# GPS.net
KiCad netlist of a schematic drawn in Altium Designer
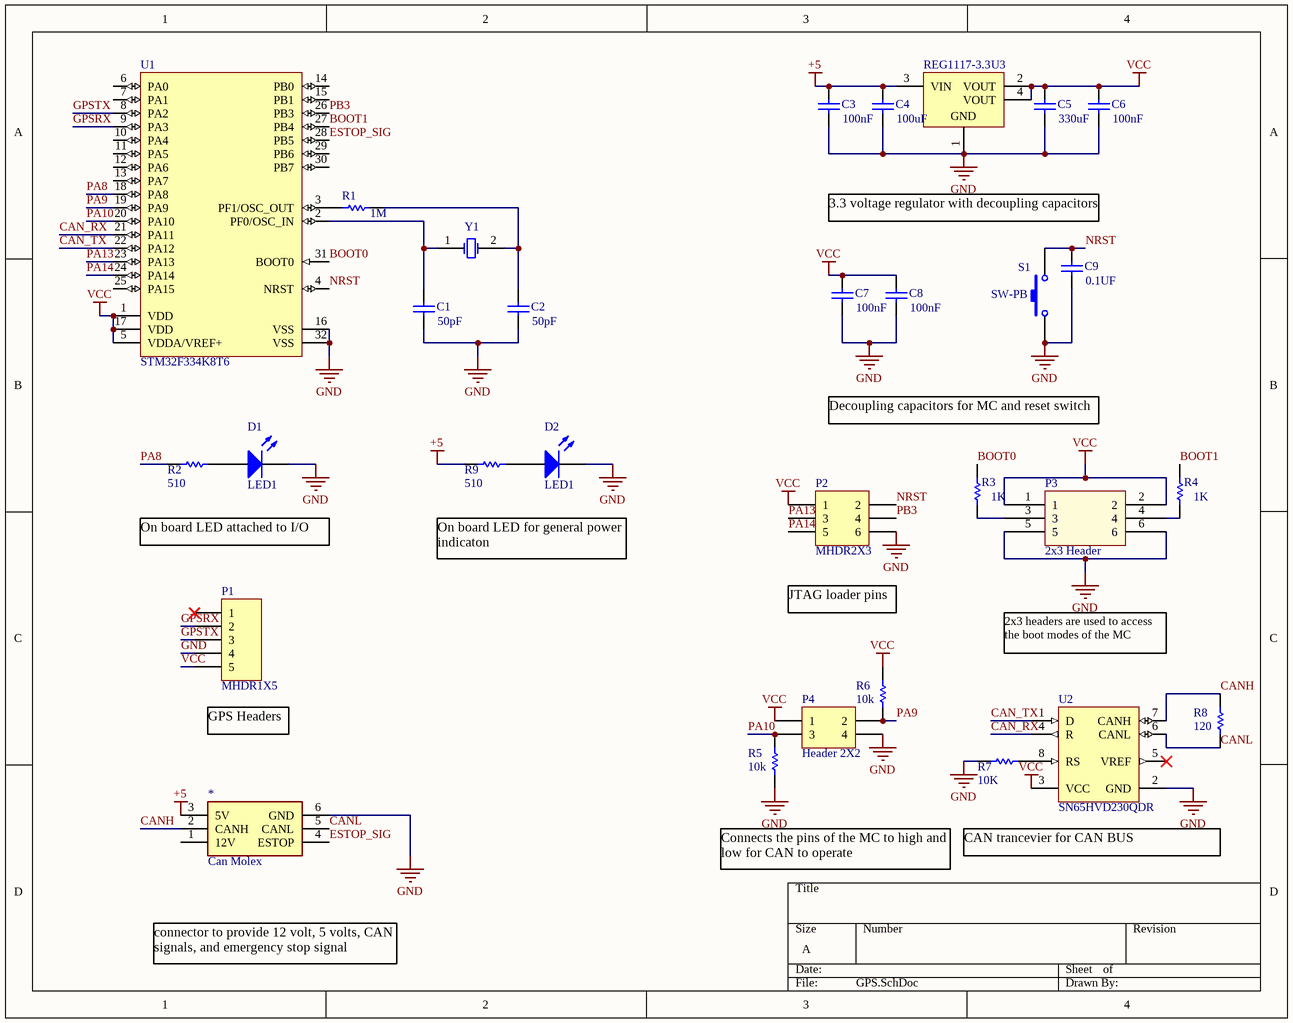
[diagram p0: GPS.SchDoc]

(export (version "E")
  (design (tool "Eeschema 10.0.6"))
  (components
    (comp (ref "*")
      (value "Can Molex")
      (footprint "Can Molex-Footprint-1")
      (description "can molex for IGVC")
      (libsource (lib "OU Competitive Robotics Club") (part "Can Molex-Symbol-1"))
    )
    (comp (ref "C1")
      (value "50pF")
      (footprint "6-0805_L")
      (description "Capacitor")
      (fields (field (name "Comment") "Cap") (field (name "PUBLISHER") "Altium Limited"))
      (libsource (lib "Miscellaneous Devices") (part "Cap"))
    )
    (comp (ref "C2")
      (value "50pF")
      (footprint "6-0805_L")
      (description "Capacitor")
      (fields (field (name "Comment") "Cap") (field (name "PUBLISHER") "Altium Limited"))
      (libsource (lib "Miscellaneous Devices") (part "Cap"))
    )
    (comp (ref "C3")
      (value "100nF")
      (footprint "6-0805_L")
      (description "Capacitor")
      (fields (field (name "Comment") "Cap") (field (name "PUBLISHER") "Altium Limited"))
      (libsource (lib "Miscellaneous Devices") (part "Cap"))
    )
    (comp (ref "C4")
      (value "100uF")
      (footprint "6-0805_L")
      (description "Capacitor")
      (fields (field (name "Comment") "Cap") (field (name "PUBLISHER") "Altium Limited"))
      (libsource (lib "Miscellaneous Devices") (part "Cap"))
    )
    (comp (ref "C5")
      (value "330uF")
      (footprint "6-0805_L")
      (description "Capacitor")
      (fields (field (name "Comment") "Cap") (field (name "PUBLISHER") "Altium Limited"))
      (libsource (lib "Miscellaneous Devices") (part "Cap"))
    )
    (comp (ref "C6")
      (value "100nF")
      (footprint "6-0805_L")
      (description "Capacitor")
      (fields (field (name "Comment") "Cap") (field (name "PUBLISHER") "Altium Limited"))
      (libsource (lib "Miscellaneous Devices") (part "Cap"))
    )
    (comp (ref "C7")
      (value "100nF")
      (footprint "6-0805_L")
      (description "Capacitor")
      (fields (field (name "Comment") "Cap") (field (name "PUBLISHER") "Altium Limited"))
      (libsource (lib "Miscellaneous Devices") (part "Cap"))
    )
    (comp (ref "C8")
      (value "100nF")
      (footprint "6-0805_L")
      (description "Capacitor")
      (fields (field (name "Comment") "Cap") (field (name "PUBLISHER") "Altium Limited"))
      (libsource (lib "Miscellaneous Devices") (part "Cap"))
    )
    (comp (ref "C9")
      (value "0.1UF")
      (footprint "6-0805_L")
      (description "Capacitor")
      (fields (field (name "Comment") "Cap") (field (name "PUBLISHER") "Altium Limited"))
      (libsource (lib "Miscellaneous Devices") (part "Cap"))
    )
    (comp (ref "D1")
      (value "LED1")
      (footprint "6-0805_L")
      (description "Typical RED GaAs LED")
      (fields (field (name "PUBLISHER") "Altium Limited"))
      (libsource (lib "Miscellaneous Devices") (part "LED1"))
    )
    (comp (ref "D2")
      (value "LED1")
      (footprint "6-0805_L")
      (description "Typical RED GaAs LED")
      (fields (field (name "PUBLISHER") "Altium Limited"))
      (libsource (lib "Miscellaneous Devices") (part "LED1"))
    )
    (comp (ref "P1")
      (value "MHDR1X5")
      (footprint "MHDR1X5")
      (description "Header, 5-Pin")
      (fields (field (name "PUBLISHER") "Altium Limited"))
      (libsource (lib "Miscellaneous Connectors") (part "MHDR1X5"))
    )
    (comp (ref "P2")
      (value "MHDR2X3")
      (footprint "HDR2X3")
      (description "Header, 3-Pin, Dual row")
      (fields (field (name "PUBLISHER") "Altium Limited"))
      (libsource (lib "Miscellaneous Connectors") (part "MHDR2X3"))
    )
    (comp (ref "P3")
      (value "2x3 Header")
      (footprint "HDR2X3")
      (libsource (lib "Schlib1") (part "2x3 Header"))
    )
    (comp (ref "P4")
      (value "Header 2X2")
      (footprint "HDR2X2")
      (description "Header, 2-Pin, Dual row")
      (fields (field (name "PUBLISHER") "Altium Limited"))
      (libsource (lib "Miscellaneous Connectors") (part "Header 2X2"))
    )
    (comp (ref "R1")
      (value "1M")
      (footprint "1608[0603]")
      (description "Resistor")
      (fields (field (name "Comment") "Res1") (field (name "PUBLISHER") "Altium Limited"))
      (libsource (lib "Miscellaneous Devices") (part "Res1"))
    )
    (comp (ref "R2")
      (value "510")
      (footprint "1608[0603]")
      (description "Resistor")
      (fields (field (name "Comment") "Res1") (field (name "PUBLISHER") "Altium Limited"))
      (libsource (lib "Miscellaneous Devices") (part "Res1"))
    )
    (comp (ref "R3")
      (value "1K")
      (footprint "1608[0603]")
      (description "Resistor")
      (fields (field (name "Comment") "Res1") (field (name "PUBLISHER") "Altium Limited"))
      (libsource (lib "Miscellaneous Devices") (part "Res1"))
    )
    (comp (ref "R4")
      (value "1K")
      (footprint "1608[0603]")
      (description "Resistor")
      (fields (field (name "Comment") "Res1") (field (name "PUBLISHER") "Altium Limited"))
      (libsource (lib "Miscellaneous Devices") (part "Res1"))
    )
    (comp (ref "R5")
      (value "10k")
      (footprint "1608[0603]")
      (description "Resistor")
      (fields (field (name "Comment") "Res1") (field (name "PUBLISHER") "Altium Limited"))
      (libsource (lib "Miscellaneous Devices") (part "Res1"))
    )
    (comp (ref "R6")
      (value "10k")
      (footprint "1608[0603]")
      (description "Resistor")
      (fields (field (name "Comment") "Res1") (field (name "PUBLISHER") "Altium Limited"))
      (libsource (lib "Miscellaneous Devices") (part "Res1"))
    )
    (comp (ref "R7")
      (value "10K")
      (footprint "1608[0603]")
      (description "Resistor")
      (fields (field (name "Comment") "Res1") (field (name "PUBLISHER") "Altium Limited"))
      (libsource (lib "Miscellaneous Devices") (part "Res1"))
    )
    (comp (ref "R8")
      (value "120")
      (footprint "1608[0603]")
      (description "Resistor")
      (fields (field (name "Comment") "Res1") (field (name "PUBLISHER") "Altium Limited"))
      (libsource (lib "Miscellaneous Devices") (part "Res1"))
    )
    (comp (ref "R9")
      (value "510")
      (footprint "1608[0603]")
      (description "Resistor")
      (fields (field (name "Comment") "Res1") (field (name "PUBLISHER") "Altium Limited"))
      (libsource (lib "Miscellaneous Devices") (part "Res1"))
    )
    (comp (ref "S1")
      (value "SW-PB")
      (footprint "GPSLib:Push Switch 3x6x2.5")
      (description "Switch")
      (fields (field (name "PUBLISHER") "Altium Limited"))
      (libsource (lib "Miscellaneous Devices") (part "SW-PB"))
    )
    (comp (ref "U1")
      (value "STM32F334K8T6")
      (footprint "STM-LQFP32_M")
      (libsource (lib "Altium Content Vault") (part "MC-ARM-STM32F334-LQFP32"))
    )
    (comp (ref "U2")
      (value "SN65HVD230QDR")
      (footprint "D0008A_L")
      (fields (field (name "MANUFACTURER") "Texas Instruments"))
      (libsource (lib "Altium Content Vault") (part "TI-SN65HVD230Q-SOIC_D-8"))
    )
    (comp (ref "U3")
      (value "REG1117-3.3")
      (footprint "DCY0004A_M")
      (fields (field (name "MANUFACTURER") "Texas Instruments"))
      (libsource (lib "Altium Content Vault") (part "TI-REG1117-XXXX"))
    )
    (comp (ref "Y1")
      (value "XTAL")
      (footprint "Crystal 11.4 x 4.7 x 4.2 mm")
      (description "Crystal Oscillator")
      (fields (field (name "PUBLISHER") "Altium Limited"))
      (libsource (lib "Miscellaneous Devices") (part "XTAL"))
    )
  )
  (nets
    (net (code "1") (name "+5") (class "Default")
      (node (ref "*") (pin "3") (pinfunction "5V_3") (pintype "passive"))
      (node (ref "C3") (pin "2") (pinfunction "2_2") (pintype "passive"))
      (node (ref "C4") (pin "2") (pinfunction "2_2") (pintype "passive"))
      (node (ref "R9") (pin "1") (pinfunction "1_1") (pintype "passive"))
      (node (ref "U3") (pin "3") (pinfunction "VIN_3") (pintype "power_in"))
    )
    (net (code "2") (name "/BOOT0") (class "Default")
      (node (ref "R3") (pin "2") (pinfunction "2_2") (pintype "passive"))
      (node (ref "U1") (pin "31") (pinfunction "BOOT0_31") (pintype "input"))
    )
    (net (code "3") (name "/BOOT1") (class "Default")
      (node (ref "R4") (pin "2") (pinfunction "2_2") (pintype "passive"))
      (node (ref "U1") (pin "27") (pinfunction "PB4_27") (pintype "bidirectional"))
    )
    (net (code "4") (name "/CANH") (class "Default")
      (node (ref "*") (pin "2") (pinfunction "CANH_2") (pintype "passive"))
      (node (ref "R8") (pin "2") (pinfunction "2_2") (pintype "passive"))
      (node (ref "U2") (pin "7") (pinfunction "CANH_7") (pintype "bidirectional"))
    )
    (net (code "5") (name "/CANL") (class "Default")
      (node (ref "*") (pin "5") (pinfunction "CANL_5") (pintype "passive"))
      (node (ref "R8") (pin "1") (pinfunction "1_1") (pintype "passive"))
      (node (ref "U2") (pin "6") (pinfunction "CANL_6") (pintype "bidirectional"))
    )
    (net (code "6") (name "/CAN_RX") (class "Default")
      (node (ref "U1") (pin "21") (pinfunction "PA11_21") (pintype "bidirectional"))
      (node (ref "U2") (pin "4") (pinfunction "R_4") (pintype "output"))
    )
    (net (code "7") (name "/CAN_TX") (class "Default")
      (node (ref "U1") (pin "22") (pinfunction "PA12_22") (pintype "bidirectional"))
      (node (ref "U2") (pin "1") (pinfunction "D_1") (pintype "input"))
    )
    (net (code "8") (name "/ESTOP_SIG") (class "Default")
      (node (ref "*") (pin "4") (pinfunction "ESTOP_4") (pintype "passive"))
      (node (ref "U1") (pin "28") (pinfunction "PB5_28") (pintype "bidirectional"))
    )
    (net (code "9") (name "/GPSRX") (class "Default")
      (node (ref "P1") (pin "2") (pinfunction "2_2") (pintype "passive"))
      (node (ref "U1") (pin "9") (pinfunction "PA3_9") (pintype "bidirectional"))
    )
    (net (code "10") (name "/GPSTX") (class "Default")
      (node (ref "P1") (pin "3") (pinfunction "3_3") (pintype "passive"))
      (node (ref "U1") (pin "8") (pinfunction "PA2_8") (pintype "bidirectional"))
    )
    (net (code "11") (name "/NRST") (class "Default")
      (node (ref "C9") (pin "2") (pinfunction "2_2") (pintype "passive"))
      (node (ref "P2") (pin "2") (pinfunction "2_2") (pintype "passive"))
      (node (ref "S1") (pin "2") (pinfunction "2_2") (pintype "passive"))
      (node (ref "U1") (pin "4") (pinfunction "NRST_4") (pintype "bidirectional"))
    )
    (net (code "12") (name "/PA8") (class "Default")
      (node (ref "R2") (pin "1") (pinfunction "1_1") (pintype "passive"))
      (node (ref "U1") (pin "18") (pinfunction "PA8_18") (pintype "bidirectional"))
    )
    (net (code "13") (name "/PA9") (class "Default")
      (node (ref "P4") (pin "2") (pinfunction "2_2") (pintype "passive"))
      (node (ref "R6") (pin "1") (pinfunction "1_1") (pintype "passive"))
      (node (ref "U1") (pin "19") (pinfunction "PA9_19") (pintype "bidirectional"))
    )
    (net (code "14") (name "/PA10") (class "Default")
      (node (ref "P4") (pin "3") (pinfunction "3_3") (pintype "passive"))
      (node (ref "R5") (pin "2") (pinfunction "2_2") (pintype "passive"))
      (node (ref "U1") (pin "20") (pinfunction "PA10_20") (pintype "bidirectional"))
    )
    (net (code "15") (name "/PA13") (class "Default")
      (node (ref "P2") (pin "3") (pinfunction "3_3") (pintype "passive"))
      (node (ref "U1") (pin "23") (pinfunction "PA13_23") (pintype "bidirectional"))
    )
    (net (code "16") (name "/PA14") (class "Default")
      (node (ref "P2") (pin "5") (pinfunction "5_5") (pintype "passive"))
      (node (ref "U1") (pin "24") (pinfunction "PA14_24") (pintype "bidirectional"))
    )
    (net (code "17") (name "/PB3") (class "Default")
      (node (ref "P2") (pin "4") (pinfunction "4_4") (pintype "passive"))
      (node (ref "U1") (pin "26") (pinfunction "PB3_26") (pintype "bidirectional"))
    )
    (net (code "18") (name "GND") (class "Default")
      (node (ref "*") (pin "6") (pinfunction "GND_6") (pintype "passive"))
      (node (ref "C1") (pin "2") (pinfunction "2_2") (pintype "passive"))
      (node (ref "C2") (pin "2") (pinfunction "2_2") (pintype "passive"))
      (node (ref "C3") (pin "1") (pinfunction "1_1") (pintype "passive"))
      (node (ref "C4") (pin "1") (pinfunction "1_1") (pintype "passive"))
      (node (ref "C5") (pin "1") (pinfunction "1_1") (pintype "passive"))
      (node (ref "C6") (pin "1") (pinfunction "1_1") (pintype "passive"))
      (node (ref "C7") (pin "1") (pinfunction "1_1") (pintype "passive"))
      (node (ref "C8") (pin "1") (pinfunction "1_1") (pintype "passive"))
      (node (ref "C9") (pin "1") (pinfunction "1_1") (pintype "passive"))
      (node (ref "D1") (pin "2") (pinfunction "K_2") (pintype "passive"))
      (node (ref "D2") (pin "2") (pinfunction "K_2") (pintype "passive"))
      (node (ref "P1") (pin "4") (pinfunction "4_4") (pintype "passive"))
      (node (ref "P2") (pin "6") (pinfunction "6_6") (pintype "passive"))
      (node (ref "P3") (pin "5") (pinfunction "5_5") (pintype "passive"))
      (node (ref "P3") (pin "6") (pinfunction "6_6") (pintype "passive"))
      (node (ref "P4") (pin "4") (pinfunction "4_4") (pintype "passive"))
      (node (ref "R5") (pin "1") (pinfunction "1_1") (pintype "passive"))
      (node (ref "R7") (pin "1") (pinfunction "1_1") (pintype "passive"))
      (node (ref "S1") (pin "1") (pinfunction "1_1") (pintype "passive"))
      (node (ref "U1") (pin "16") (pinfunction "VSS_16") (pintype "power_in"))
      (node (ref "U1") (pin "32") (pinfunction "VSS_32") (pintype "power_in"))
      (node (ref "U2") (pin "2") (pinfunction "GND_2") (pintype "power_in"))
      (node (ref "U3") (pin "1") (pinfunction "GND_1") (pintype "power_in"))
    )
    (net (code "19") (name "Net-(D1-A)") (class "Default")
      (node (ref "D1") (pin "1") (pinfunction "A_1") (pintype "passive"))
      (node (ref "R2") (pin "2") (pinfunction "2_2") (pintype "passive"))
    )
    (net (code "20") (name "Net-(D2-A)") (class "Default")
      (node (ref "D2") (pin "1") (pinfunction "A_1") (pintype "passive"))
      (node (ref "R9") (pin "2") (pinfunction "2_2") (pintype "passive"))
    )
    (net (code "21") (name "Net-(P3-Pad3)") (class "Default")
      (node (ref "P3") (pin "3") (pinfunction "3_3") (pintype "passive"))
      (node (ref "R3") (pin "1") (pinfunction "1_1") (pintype "passive"))
    )
    (net (code "22") (name "Net-(P3-Pad4)") (class "Default")
      (node (ref "P3") (pin "4") (pinfunction "4_4") (pintype "passive"))
      (node (ref "R4") (pin "1") (pinfunction "1_1") (pintype "passive"))
    )
    (net (code "23") (name "Net-(U1-PF0{slash}OSC_IN)") (class "Default")
      (node (ref "C1") (pin "1") (pinfunction "1_1") (pintype "passive"))
      (node (ref "U1") (pin "2") (pinfunction "PF0/OSC_IN_2") (pintype "bidirectional"))
      (node (ref "Y1") (pin "1") (pinfunction "OSC1_1") (pintype "passive"))
    )
    (net (code "24") (name "Net-(U1-PF1{slash}OSC_OUT)") (class "Default")
      (node (ref "R1") (pin "1") (pinfunction "1_1") (pintype "passive"))
      (node (ref "U1") (pin "3") (pinfunction "PF1/OSC_OUT_3") (pintype "bidirectional"))
    )
    (net (code "25") (name "Net-(U2-RS)") (class "Default")
      (node (ref "R7") (pin "2") (pinfunction "2_2") (pintype "passive"))
      (node (ref "U2") (pin "8") (pinfunction "RS_8") (pintype "input"))
    )
    (net (code "26") (name "Net-(Y1-OSC2)") (class "Default")
      (node (ref "C2") (pin "1") (pinfunction "1_1") (pintype "passive"))
      (node (ref "R1") (pin "2") (pinfunction "2_2") (pintype "passive"))
      (node (ref "Y1") (pin "2") (pinfunction "OSC2_2") (pintype "passive"))
    )
    (net (code "27") (name "VCC") (class "Default")
      (node (ref "C5") (pin "2") (pinfunction "2_2") (pintype "passive"))
      (node (ref "C6") (pin "2") (pinfunction "2_2") (pintype "passive"))
      (node (ref "C7") (pin "2") (pinfunction "2_2") (pintype "passive"))
      (node (ref "C8") (pin "2") (pinfunction "2_2") (pintype "passive"))
      (node (ref "P1") (pin "5") (pinfunction "5_5") (pintype "passive"))
      (node (ref "P2") (pin "1") (pinfunction "1_1") (pintype "passive"))
      (node (ref "P3") (pin "1") (pinfunction "1_1") (pintype "passive"))
      (node (ref "P3") (pin "2") (pinfunction "2_2") (pintype "passive"))
      (node (ref "P4") (pin "1") (pinfunction "1_1") (pintype "passive"))
      (node (ref "R6") (pin "2") (pinfunction "2_2") (pintype "passive"))
      (node (ref "U1") (pin "1") (pinfunction "VDD_1") (pintype "power_in"))
      (node (ref "U1") (pin "17") (pinfunction "VDD_17") (pintype "power_in"))
      (node (ref "U1") (pin "5") (pinfunction "VDDA/VREF+_5") (pintype "power_in"))
      (node (ref "U2") (pin "3") (pinfunction "VCC_3") (pintype "power_in"))
      (node (ref "U3") (pin "2") (pinfunction "VOUT_2") (pintype "power_in"))
      (node (ref "U3") (pin "4") (pinfunction "VOUT_4") (pintype "power_in"))
    )
    (net (code "28") (name "unconnected-(*-12V-Pad1)") (class "Default")
      (node (ref "*") (pin "1") (pinfunction "12V_1") (pintype "passive"))
    )
    (net (code "29") (name "unconnected-(P1-Pad1)") (class "Default")
      (node (ref "P1") (pin "1") (pinfunction "1_1") (pintype "passive+no_connect"))
    )
    (net (code "30") (name "unconnected-(U1-PA0-Pad6)") (class "Default")
      (node (ref "U1") (pin "6") (pinfunction "PA0_6") (pintype "bidirectional"))
    )
    (net (code "31") (name "unconnected-(U1-PA1-Pad7)") (class "Default")
      (node (ref "U1") (pin "7") (pinfunction "PA1_7") (pintype "bidirectional"))
    )
    (net (code "32") (name "unconnected-(U1-PA4-Pad10)") (class "Default")
      (node (ref "U1") (pin "10") (pinfunction "PA4_10") (pintype "bidirectional"))
    )
    (net (code "33") (name "unconnected-(U1-PA5-Pad11)") (class "Default")
      (node (ref "U1") (pin "11") (pinfunction "PA5_11") (pintype "bidirectional"))
    )
    (net (code "34") (name "unconnected-(U1-PA6-Pad12)") (class "Default")
      (node (ref "U1") (pin "12") (pinfunction "PA6_12") (pintype "bidirectional"))
    )
    (net (code "35") (name "unconnected-(U1-PA7-Pad13)") (class "Default")
      (node (ref "U1") (pin "13") (pinfunction "PA7_13") (pintype "bidirectional"))
    )
    (net (code "36") (name "unconnected-(U1-PA15-Pad25)") (class "Default")
      (node (ref "U1") (pin "25") (pinfunction "PA15_25") (pintype "bidirectional"))
    )
    (net (code "37") (name "unconnected-(U1-PB0-Pad14)") (class "Default")
      (node (ref "U1") (pin "14") (pinfunction "PB0_14") (pintype "bidirectional"))
    )
    (net (code "38") (name "unconnected-(U1-PB1-Pad15)") (class "Default")
      (node (ref "U1") (pin "15") (pinfunction "PB1_15") (pintype "bidirectional"))
    )
    (net (code "39") (name "unconnected-(U1-PB6-Pad29)") (class "Default")
      (node (ref "U1") (pin "29") (pinfunction "PB6_29") (pintype "bidirectional"))
    )
    (net (code "40") (name "unconnected-(U1-PB7-Pad30)") (class "Default")
      (node (ref "U1") (pin "30") (pinfunction "PB7_30") (pintype "bidirectional"))
    )
    (net (code "41") (name "unconnected-(U2-VREF-Pad5)") (class "Default")
      (node (ref "U2") (pin "5") (pinfunction "VREF_5") (pintype "output+no_connect"))
    )
  )
)
